# ASBB_WheelSpeed.net
KiCad netlist of a schematic drawn in Altium Designer
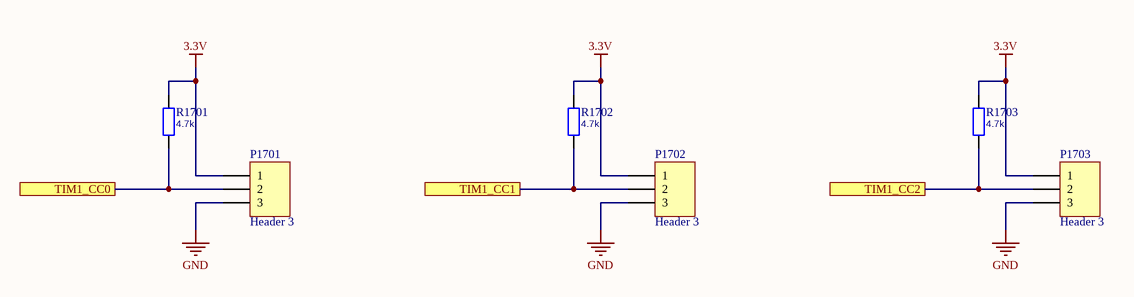
[diagram p0: ASBB_WheelSpeed.SchDoc]

(export (version "E")
  (design (tool "Eeschema 10.0.6"))
  (components
    (comp (ref "P1701")
      (value "Header 3")
      (footprint "HDR1X3")
      (description "Header, 3-Pin")
      (fields (field (name "PUBLISHER") "Altium Limited"))
      (libsource (lib "Miscellaneous Connectors") (part "Header 3"))
    )
    (comp (ref "P1702")
      (value "Header 3")
      (footprint "HDR1X3")
      (description "Header, 3-Pin")
      (fields (field (name "PUBLISHER") "Altium Limited"))
      (libsource (lib "Miscellaneous Connectors") (part "Header 3"))
    )
    (comp (ref "P1703")
      (value "Header 3")
      (footprint "HDR1X3")
      (description "Header, 3-Pin")
      (fields (field (name "PUBLISHER") "Altium Limited"))
      (libsource (lib "Miscellaneous Connectors") (part "Header 3"))
    )
    (comp (ref "R1701")
      (value "4.7k")
      (footprint "0603")
      (description "Resistor")
      (fields (field (name "PARTNUMBER") "?"))
      (libsource (lib "FZI") (part "Resistor"))
    )
    (comp (ref "R1702")
      (value "4.7k")
      (footprint "0603")
      (description "Resistor")
      (fields (field (name "PARTNUMBER") "?"))
      (libsource (lib "FZI") (part "Resistor"))
    )
    (comp (ref "R1703")
      (value "4.7k")
      (footprint "0603")
      (description "Resistor")
      (fields (field (name "PARTNUMBER") "?"))
      (libsource (lib "FZI") (part "Resistor"))
    )
  )
  (nets
    (net (code "1") (name "/TIM1_CC0") (class "Default")
      (node (ref "P1701") (pin "2") (pinfunction "2_2") (pintype "passive"))
      (node (ref "R1701") (pin "1") (pinfunction "1_1") (pintype "passive"))
    )
    (net (code "2") (name "/TIM1_CC1") (class "Default")
      (node (ref "P1702") (pin "2") (pinfunction "2_2") (pintype "passive"))
      (node (ref "R1702") (pin "1") (pinfunction "1_1") (pintype "passive"))
    )
    (net (code "3") (name "/TIM1_CC2") (class "Default")
      (node (ref "P1703") (pin "2") (pinfunction "2_2") (pintype "passive"))
      (node (ref "R1703") (pin "1") (pinfunction "1_1") (pintype "passive"))
    )
    (net (code "4") (name "3.3V") (class "Default")
      (node (ref "P1701") (pin "1") (pinfunction "1_1") (pintype "passive"))
      (node (ref "P1702") (pin "1") (pinfunction "1_1") (pintype "passive"))
      (node (ref "P1703") (pin "1") (pinfunction "1_1") (pintype "passive"))
      (node (ref "R1701") (pin "2") (pinfunction "2_2") (pintype "passive"))
      (node (ref "R1702") (pin "2") (pinfunction "2_2") (pintype "passive"))
      (node (ref "R1703") (pin "2") (pinfunction "2_2") (pintype "passive"))
    )
    (net (code "5") (name "GND") (class "Default")
      (node (ref "P1701") (pin "3") (pinfunction "3_3") (pintype "passive"))
      (node (ref "P1702") (pin "3") (pinfunction "3_3") (pintype "passive"))
      (node (ref "P1703") (pin "3") (pinfunction "3_3") (pintype "passive"))
    )
  )
)
